# mso5000_analyzer.net
KiCad netlist of a schematic drawn in EAGLE
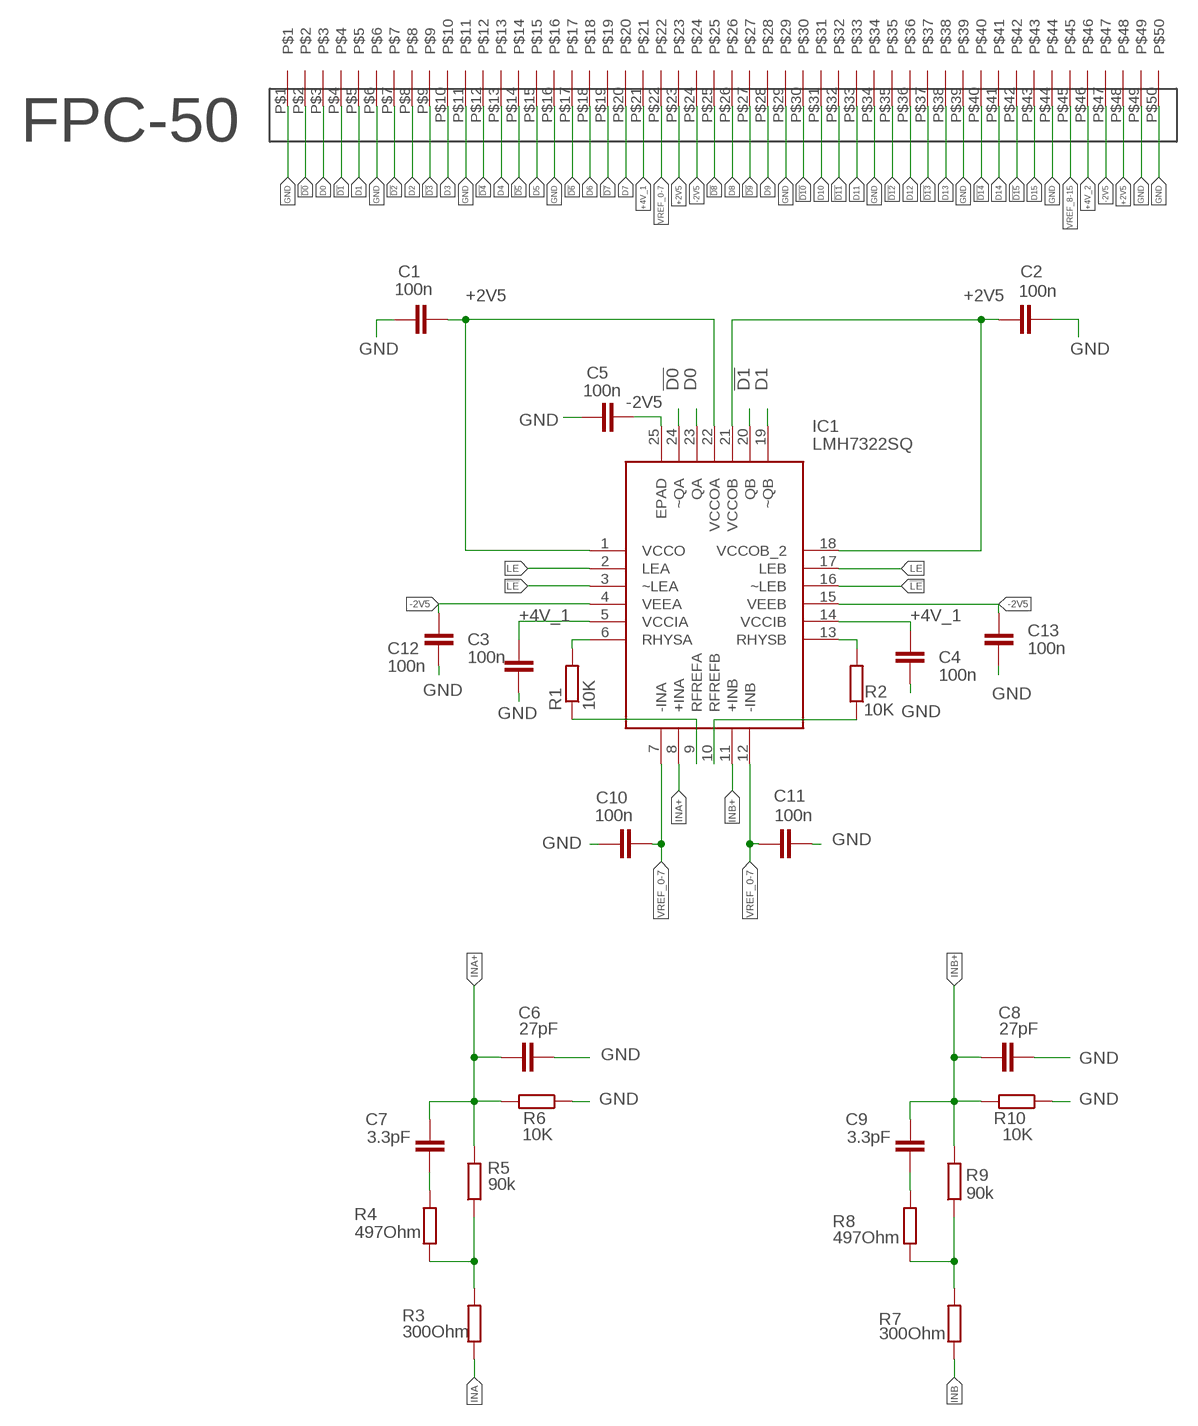
[diagram p0: schematic, sheet 1]

(export (version "E")
  (design (tool "Eeschema 10.0.6"))
  (components
    (comp (ref "C1")
      (value "100n")
      (footprint "eagle-import:C0805")
      (libsource (lib "eagle-import") (part "C-EUC0805"))
    )
    (comp (ref "C2")
      (value "100n")
      (footprint "eagle-import:C0805")
      (libsource (lib "eagle-import") (part "C-EUC0805"))
    )
    (comp (ref "C3")
      (value "100n")
      (footprint "eagle-import:C0805")
      (libsource (lib "eagle-import") (part "C-EUC0805"))
    )
    (comp (ref "C4")
      (value "100n")
      (footprint "eagle-import:C0805")
      (libsource (lib "eagle-import") (part "C-EUC0805"))
    )
    (comp (ref "C5")
      (value "100n")
      (footprint "eagle-import:C0805")
      (libsource (lib "eagle-import") (part "C-EUC0805"))
    )
    (comp (ref "C6")
      (value "27pF")
      (footprint "eagle-import:C0805")
      (libsource (lib "eagle-import") (part "C-EUC0805"))
    )
    (comp (ref "C7")
      (value "3.3pF")
      (footprint "eagle-import:C0805")
      (libsource (lib "eagle-import") (part "C-EUC0805"))
    )
    (comp (ref "C8")
      (value "27pF")
      (footprint "eagle-import:C0805")
      (libsource (lib "eagle-import") (part "C-EUC0805"))
    )
    (comp (ref "C9")
      (value "3.3pF")
      (footprint "eagle-import:C0805")
      (libsource (lib "eagle-import") (part "C-EUC0805"))
    )
    (comp (ref "C10")
      (value "100n")
      (footprint "eagle-import:C0805")
      (libsource (lib "eagle-import") (part "C-EUC0805"))
    )
    (comp (ref "C11")
      (value "100n")
      (footprint "eagle-import:C0805")
      (libsource (lib "eagle-import") (part "C-EUC0805"))
    )
    (comp (ref "C12")
      (value "100n")
      (footprint "eagle-import:C0805")
      (libsource (lib "eagle-import") (part "C-EUC0805"))
    )
    (comp (ref "C13")
      (value "100n")
      (footprint "eagle-import:C0805")
      (libsource (lib "eagle-import") (part "C-EUC0805"))
    )
    (comp (ref "FPC-50")
      (value "ZIFF-050")
      (footprint "eagle-import:ZIFF-050")
      (libsource (lib "eagle-import") (part "ZIFF-050"))
    )
    (comp (ref "IC1")
      (value "LMH7322SQ")
      (footprint "eagle-import:QFN50P400X400X80-25N")
      (libsource (lib "eagle-import") (part "LMH7322SQ"))
    )
    (comp (ref "R1")
      (value "10K")
      (footprint "eagle-import:R0805")
      (libsource (lib "eagle-import") (part "R-EU_R0805"))
    )
    (comp (ref "R2")
      (value "10K")
      (footprint "eagle-import:R0805")
      (libsource (lib "eagle-import") (part "R-EU_R0805"))
    )
    (comp (ref "R3")
      (value "300Ohm")
      (footprint "eagle-import:R0805")
      (libsource (lib "eagle-import") (part "R-EU_R0805"))
    )
    (comp (ref "R4")
      (value "497Ohm")
      (footprint "eagle-import:R0805")
      (libsource (lib "eagle-import") (part "R-EU_R0805"))
    )
    (comp (ref "R5")
      (value "90k")
      (footprint "eagle-import:R0805")
      (libsource (lib "eagle-import") (part "R-EU_R0805"))
    )
    (comp (ref "R6")
      (value "10K")
      (footprint "eagle-import:R0805")
      (libsource (lib "eagle-import") (part "R-EU_R0805"))
    )
    (comp (ref "R7")
      (value "300Ohm")
      (footprint "eagle-import:R0805")
      (libsource (lib "eagle-import") (part "R-EU_R0805"))
    )
    (comp (ref "R8")
      (value "497Ohm")
      (footprint "eagle-import:R0805")
      (libsource (lib "eagle-import") (part "R-EU_R0805"))
    )
    (comp (ref "R9")
      (value "90k")
      (footprint "eagle-import:R0805")
      (libsource (lib "eagle-import") (part "R-EU_R0805"))
    )
    (comp (ref "R10")
      (value "10K")
      (footprint "eagle-import:R0805")
      (libsource (lib "eagle-import") (part "R-EU_R0805"))
    )
  )
  (nets
    (net (code "1") (name "+2V5") (class "Default")
      (node (ref "C1") (pin "1") (pinfunction "1_1") (pintype "passive"))
      (node (ref "C2") (pin "2") (pinfunction "2_2") (pintype "passive"))
      (node (ref "FPC-50") (pin "P$23") (pinfunction "P$23_P$23") (pintype "bidirectional"))
      (node (ref "FPC-50") (pin "P$48") (pinfunction "P$48_P$48") (pintype "bidirectional"))
      (node (ref "IC1") (pin "1") (pinfunction "VCCO_1") (pintype "bidirectional"))
      (node (ref "IC1") (pin "18") (pinfunction "VCCOB_2_18") (pintype "bidirectional"))
      (node (ref "IC1") (pin "21") (pinfunction "VCCOB_21") (pintype "bidirectional"))
      (node (ref "IC1") (pin "22") (pinfunction "VCCOA_22") (pintype "bidirectional"))
    )
    (net (code "2") (name "+4V_1") (class "Default")
      (node (ref "C3") (pin "1") (pinfunction "1_1") (pintype "passive"))
      (node (ref "C4") (pin "1") (pinfunction "1_1") (pintype "passive"))
      (node (ref "FPC-50") (pin "P$21") (pinfunction "P$21_P$21") (pintype "bidirectional"))
      (node (ref "IC1") (pin "14") (pinfunction "VCCIB_14") (pintype "bidirectional"))
      (node (ref "IC1") (pin "5") (pinfunction "VCCIA_5") (pintype "bidirectional"))
    )
    (net (code "3") (name "+4V_2") (class "Default")
      (node (ref "FPC-50") (pin "P$46") (pinfunction "P$46_P$46") (pintype "bidirectional"))
    )
    (net (code "4") (name "-2V5") (class "Default")
      (node (ref "C12") (pin "1") (pinfunction "1_1") (pintype "passive"))
      (node (ref "C13") (pin "1") (pinfunction "1_1") (pintype "passive"))
      (node (ref "C5") (pin "1") (pinfunction "1_1") (pintype "passive"))
      (node (ref "FPC-50") (pin "P$24") (pinfunction "P$24_P$24") (pintype "bidirectional"))
      (node (ref "FPC-50") (pin "P$47") (pinfunction "P$47_P$47") (pintype "bidirectional"))
      (node (ref "IC1") (pin "15") (pinfunction "VEEB_15") (pintype "bidirectional"))
      (node (ref "IC1") (pin "25") (pinfunction "EPAD_25") (pintype "bidirectional"))
      (node (ref "IC1") (pin "4") (pinfunction "VEEA_4") (pintype "bidirectional"))
    )
    (net (code "5") (name "/~{D0}") (class "Default")
      (node (ref "FPC-50") (pin "P$2") (pinfunction "P$2_P$2") (pintype "bidirectional"))
      (node (ref "IC1") (pin "24") (pinfunction "~{QA}_24") (pintype "bidirectional"))
    )
    (net (code "6") (name "/~{D1}") (class "Default")
      (node (ref "FPC-50") (pin "P$4") (pinfunction "P$4_P$4") (pintype "bidirectional"))
      (node (ref "IC1") (pin "20") (pinfunction "QB_20") (pintype "bidirectional"))
    )
    (net (code "7") (name "/~{D2}") (class "Default")
      (node (ref "FPC-50") (pin "P$7") (pinfunction "P$7_P$7") (pintype "bidirectional"))
    )
    (net (code "8") (name "/~{D3}") (class "Default")
      (node (ref "FPC-50") (pin "P$9") (pinfunction "P$9_P$9") (pintype "bidirectional"))
    )
    (net (code "9") (name "/~{D4}") (class "Default")
      (node (ref "FPC-50") (pin "P$12") (pinfunction "P$12_P$12") (pintype "bidirectional"))
    )
    (net (code "10") (name "/~{D5}") (class "Default")
      (node (ref "FPC-50") (pin "P$14") (pinfunction "P$14_P$14") (pintype "bidirectional"))
    )
    (net (code "11") (name "/~{D6}") (class "Default")
      (node (ref "FPC-50") (pin "P$17") (pinfunction "P$17_P$17") (pintype "bidirectional"))
    )
    (net (code "12") (name "/~{D7}") (class "Default")
      (node (ref "FPC-50") (pin "P$19") (pinfunction "P$19_P$19") (pintype "bidirectional"))
    )
    (net (code "13") (name "/~{D8}") (class "Default")
      (node (ref "FPC-50") (pin "P$25") (pinfunction "P$25_P$25") (pintype "bidirectional"))
    )
    (net (code "14") (name "/~{D9}") (class "Default")
      (node (ref "FPC-50") (pin "P$27") (pinfunction "P$27_P$27") (pintype "bidirectional"))
    )
    (net (code "15") (name "/~{D10}") (class "Default")
      (node (ref "FPC-50") (pin "P$30") (pinfunction "P$30_P$30") (pintype "bidirectional"))
    )
    (net (code "16") (name "/~{D11}") (class "Default")
      (node (ref "FPC-50") (pin "P$32") (pinfunction "P$32_P$32") (pintype "bidirectional"))
    )
    (net (code "17") (name "/~{D12}") (class "Default")
      (node (ref "FPC-50") (pin "P$35") (pinfunction "P$35_P$35") (pintype "bidirectional"))
    )
    (net (code "18") (name "/~{D13}") (class "Default")
      (node (ref "FPC-50") (pin "P$37") (pinfunction "P$37_P$37") (pintype "bidirectional"))
    )
    (net (code "19") (name "/~{D14}") (class "Default")
      (node (ref "FPC-50") (pin "P$40") (pinfunction "P$40_P$40") (pintype "bidirectional"))
    )
    (net (code "20") (name "/~{D15}") (class "Default")
      (node (ref "FPC-50") (pin "P$42") (pinfunction "P$42_P$42") (pintype "bidirectional"))
    )
    (net (code "21") (name "/~{LE}") (class "Default")
      (node (ref "IC1") (pin "16") (pinfunction "~{LEB}_16") (pintype "bidirectional"))
      (node (ref "IC1") (pin "3") (pinfunction "~{LEA}_3") (pintype "bidirectional"))
    )
    (net (code "22") (name "D0") (class "Default")
      (node (ref "FPC-50") (pin "P$3") (pinfunction "P$3_P$3") (pintype "bidirectional"))
      (node (ref "IC1") (pin "23") (pinfunction "QA_23") (pintype "bidirectional"))
    )
    (net (code "23") (name "D1") (class "Default")
      (node (ref "FPC-50") (pin "P$5") (pinfunction "P$5_P$5") (pintype "bidirectional"))
      (node (ref "IC1") (pin "19") (pinfunction "~{QB}_19") (pintype "bidirectional"))
    )
    (net (code "24") (name "D2") (class "Default")
      (node (ref "FPC-50") (pin "P$8") (pinfunction "P$8_P$8") (pintype "bidirectional"))
    )
    (net (code "25") (name "D3") (class "Default")
      (node (ref "FPC-50") (pin "P$10") (pinfunction "P$10_P$10") (pintype "bidirectional"))
    )
    (net (code "26") (name "D4") (class "Default")
      (node (ref "FPC-50") (pin "P$13") (pinfunction "P$13_P$13") (pintype "bidirectional"))
    )
    (net (code "27") (name "D5") (class "Default")
      (node (ref "FPC-50") (pin "P$15") (pinfunction "P$15_P$15") (pintype "bidirectional"))
    )
    (net (code "28") (name "D6") (class "Default")
      (node (ref "FPC-50") (pin "P$18") (pinfunction "P$18_P$18") (pintype "bidirectional"))
    )
    (net (code "29") (name "D7") (class "Default")
      (node (ref "FPC-50") (pin "P$20") (pinfunction "P$20_P$20") (pintype "bidirectional"))
    )
    (net (code "30") (name "D8") (class "Default")
      (node (ref "FPC-50") (pin "P$26") (pinfunction "P$26_P$26") (pintype "bidirectional"))
    )
    (net (code "31") (name "D9") (class "Default")
      (node (ref "FPC-50") (pin "P$28") (pinfunction "P$28_P$28") (pintype "bidirectional"))
    )
    (net (code "32") (name "D10") (class "Default")
      (node (ref "FPC-50") (pin "P$31") (pinfunction "P$31_P$31") (pintype "bidirectional"))
    )
    (net (code "33") (name "D11") (class "Default")
      (node (ref "FPC-50") (pin "P$33") (pinfunction "P$33_P$33") (pintype "bidirectional"))
    )
    (net (code "34") (name "D12") (class "Default")
      (node (ref "FPC-50") (pin "P$36") (pinfunction "P$36_P$36") (pintype "bidirectional"))
    )
    (net (code "35") (name "D13") (class "Default")
      (node (ref "FPC-50") (pin "P$38") (pinfunction "P$38_P$38") (pintype "bidirectional"))
    )
    (net (code "36") (name "D14") (class "Default")
      (node (ref "FPC-50") (pin "P$41") (pinfunction "P$41_P$41") (pintype "bidirectional"))
    )
    (net (code "37") (name "D15") (class "Default")
      (node (ref "FPC-50") (pin "P$43") (pinfunction "P$43_P$43") (pintype "bidirectional"))
    )
    (net (code "38") (name "GND") (class "Default")
      (node (ref "C1") (pin "2") (pinfunction "2_2") (pintype "passive"))
      (node (ref "C10") (pin "1") (pinfunction "1_1") (pintype "passive"))
      (node (ref "C11") (pin "2") (pinfunction "2_2") (pintype "passive"))
      (node (ref "C12") (pin "2") (pinfunction "2_2") (pintype "passive"))
      (node (ref "C13") (pin "2") (pinfunction "2_2") (pintype "passive"))
      (node (ref "C2") (pin "1") (pinfunction "1_1") (pintype "passive"))
      (node (ref "C3") (pin "2") (pinfunction "2_2") (pintype "passive"))
      (node (ref "C4") (pin "2") (pinfunction "2_2") (pintype "passive"))
      (node (ref "C5") (pin "2") (pinfunction "2_2") (pintype "passive"))
      (node (ref "C6") (pin "2") (pinfunction "2_2") (pintype "passive"))
      (node (ref "C8") (pin "2") (pinfunction "2_2") (pintype "passive"))
      (node (ref "FPC-50") (pin "P$1") (pinfunction "P$1_P$1") (pintype "bidirectional"))
      (node (ref "FPC-50") (pin "P$11") (pinfunction "P$11_P$11") (pintype "bidirectional"))
      (node (ref "FPC-50") (pin "P$16") (pinfunction "P$16_P$16") (pintype "bidirectional"))
      (node (ref "FPC-50") (pin "P$29") (pinfunction "P$29_P$29") (pintype "bidirectional"))
      (node (ref "FPC-50") (pin "P$34") (pinfunction "P$34_P$34") (pintype "bidirectional"))
      (node (ref "FPC-50") (pin "P$39") (pinfunction "P$39_P$39") (pintype "bidirectional"))
      (node (ref "FPC-50") (pin "P$44") (pinfunction "P$44_P$44") (pintype "bidirectional"))
      (node (ref "FPC-50") (pin "P$49") (pinfunction "P$49_P$49") (pintype "bidirectional"))
      (node (ref "FPC-50") (pin "P$50") (pinfunction "P$50_P$50") (pintype "bidirectional"))
      (node (ref "FPC-50") (pin "P$6") (pinfunction "P$6_P$6") (pintype "bidirectional"))
      (node (ref "R10") (pin "1") (pinfunction "1_1") (pintype "passive"))
      (node (ref "R6") (pin "1") (pinfunction "1_1") (pintype "passive"))
    )
    (net (code "39") (name "INA") (class "Default")
      (node (ref "R3") (pin "1") (pinfunction "1_1") (pintype "passive"))
    )
    (net (code "40") (name "INA+") (class "Default")
      (node (ref "C6") (pin "1") (pinfunction "1_1") (pintype "passive"))
      (node (ref "C7") (pin "2") (pinfunction "2_2") (pintype "passive"))
      (node (ref "IC1") (pin "8") (pinfunction "+INA_8") (pintype "bidirectional"))
      (node (ref "R5") (pin "2") (pinfunction "2_2") (pintype "passive"))
      (node (ref "R6") (pin "2") (pinfunction "2_2") (pintype "passive"))
    )
    (net (code "41") (name "INB") (class "Default")
      (node (ref "R7") (pin "1") (pinfunction "1_1") (pintype "passive"))
    )
    (net (code "42") (name "INB+") (class "Default")
      (node (ref "C8") (pin "1") (pinfunction "1_1") (pintype "passive"))
      (node (ref "C9") (pin "2") (pinfunction "2_2") (pintype "passive"))
      (node (ref "IC1") (pin "11") (pinfunction "+INB_11") (pintype "bidirectional"))
      (node (ref "R10") (pin "2") (pinfunction "2_2") (pintype "passive"))
      (node (ref "R9") (pin "2") (pinfunction "2_2") (pintype "passive"))
    )
    (net (code "43") (name "LE") (class "Default")
      (node (ref "IC1") (pin "17") (pinfunction "LEB_17") (pintype "bidirectional"))
      (node (ref "IC1") (pin "2") (pinfunction "LEA_2") (pintype "bidirectional"))
    )
    (net (code "44") (name "Net-(C7-Pad1)") (class "Default")
      (node (ref "C7") (pin "1") (pinfunction "1_1") (pintype "passive"))
      (node (ref "R4") (pin "2") (pinfunction "2_2") (pintype "passive"))
    )
    (net (code "45") (name "Net-(C9-Pad1)") (class "Default")
      (node (ref "C9") (pin "1") (pinfunction "1_1") (pintype "passive"))
      (node (ref "R8") (pin "2") (pinfunction "2_2") (pintype "passive"))
    )
    (net (code "46") (name "Net-(IC1-RFREFA)") (class "Default")
      (node (ref "IC1") (pin "9") (pinfunction "RFREFA_9") (pintype "bidirectional"))
      (node (ref "R1") (pin "1") (pinfunction "1_1") (pintype "passive"))
    )
    (net (code "47") (name "Net-(IC1-RFREFB)") (class "Default")
      (node (ref "IC1") (pin "10") (pinfunction "RFREFB_10") (pintype "bidirectional"))
      (node (ref "R2") (pin "1") (pinfunction "1_1") (pintype "passive"))
    )
    (net (code "48") (name "Net-(IC1-RHYSA)") (class "Default")
      (node (ref "IC1") (pin "6") (pinfunction "RHYSA_6") (pintype "bidirectional"))
      (node (ref "R1") (pin "2") (pinfunction "2_2") (pintype "passive"))
    )
    (net (code "49") (name "Net-(IC1-RHYSB)") (class "Default")
      (node (ref "IC1") (pin "13") (pinfunction "RHYSB_13") (pintype "bidirectional"))
      (node (ref "R2") (pin "2") (pinfunction "2_2") (pintype "passive"))
    )
    (net (code "50") (name "Net-(R3-Pad2)") (class "Default")
      (node (ref "R3") (pin "2") (pinfunction "2_2") (pintype "passive"))
      (node (ref "R4") (pin "1") (pinfunction "1_1") (pintype "passive"))
      (node (ref "R5") (pin "1") (pinfunction "1_1") (pintype "passive"))
    )
    (net (code "51") (name "Net-(R7-Pad2)") (class "Default")
      (node (ref "R7") (pin "2") (pinfunction "2_2") (pintype "passive"))
      (node (ref "R8") (pin "1") (pinfunction "1_1") (pintype "passive"))
      (node (ref "R9") (pin "1") (pinfunction "1_1") (pintype "passive"))
    )
    (net (code "52") (name "VREF_0-7") (class "Default")
      (node (ref "C10") (pin "2") (pinfunction "2_2") (pintype "passive"))
      (node (ref "C11") (pin "1") (pinfunction "1_1") (pintype "passive"))
      (node (ref "FPC-50") (pin "P$22") (pinfunction "P$22_P$22") (pintype "bidirectional"))
      (node (ref "IC1") (pin "12") (pinfunction "-INB_12") (pintype "bidirectional"))
      (node (ref "IC1") (pin "7") (pinfunction "-INA_7") (pintype "bidirectional"))
    )
    (net (code "53") (name "VREF_8-15") (class "Default")
      (node (ref "FPC-50") (pin "P$45") (pinfunction "P$45_P$45") (pintype "bidirectional"))
    )
  )
)
